# ESPrucherLoraScale7802.net
KiCad netlist of a schematic drawn in EAGLE
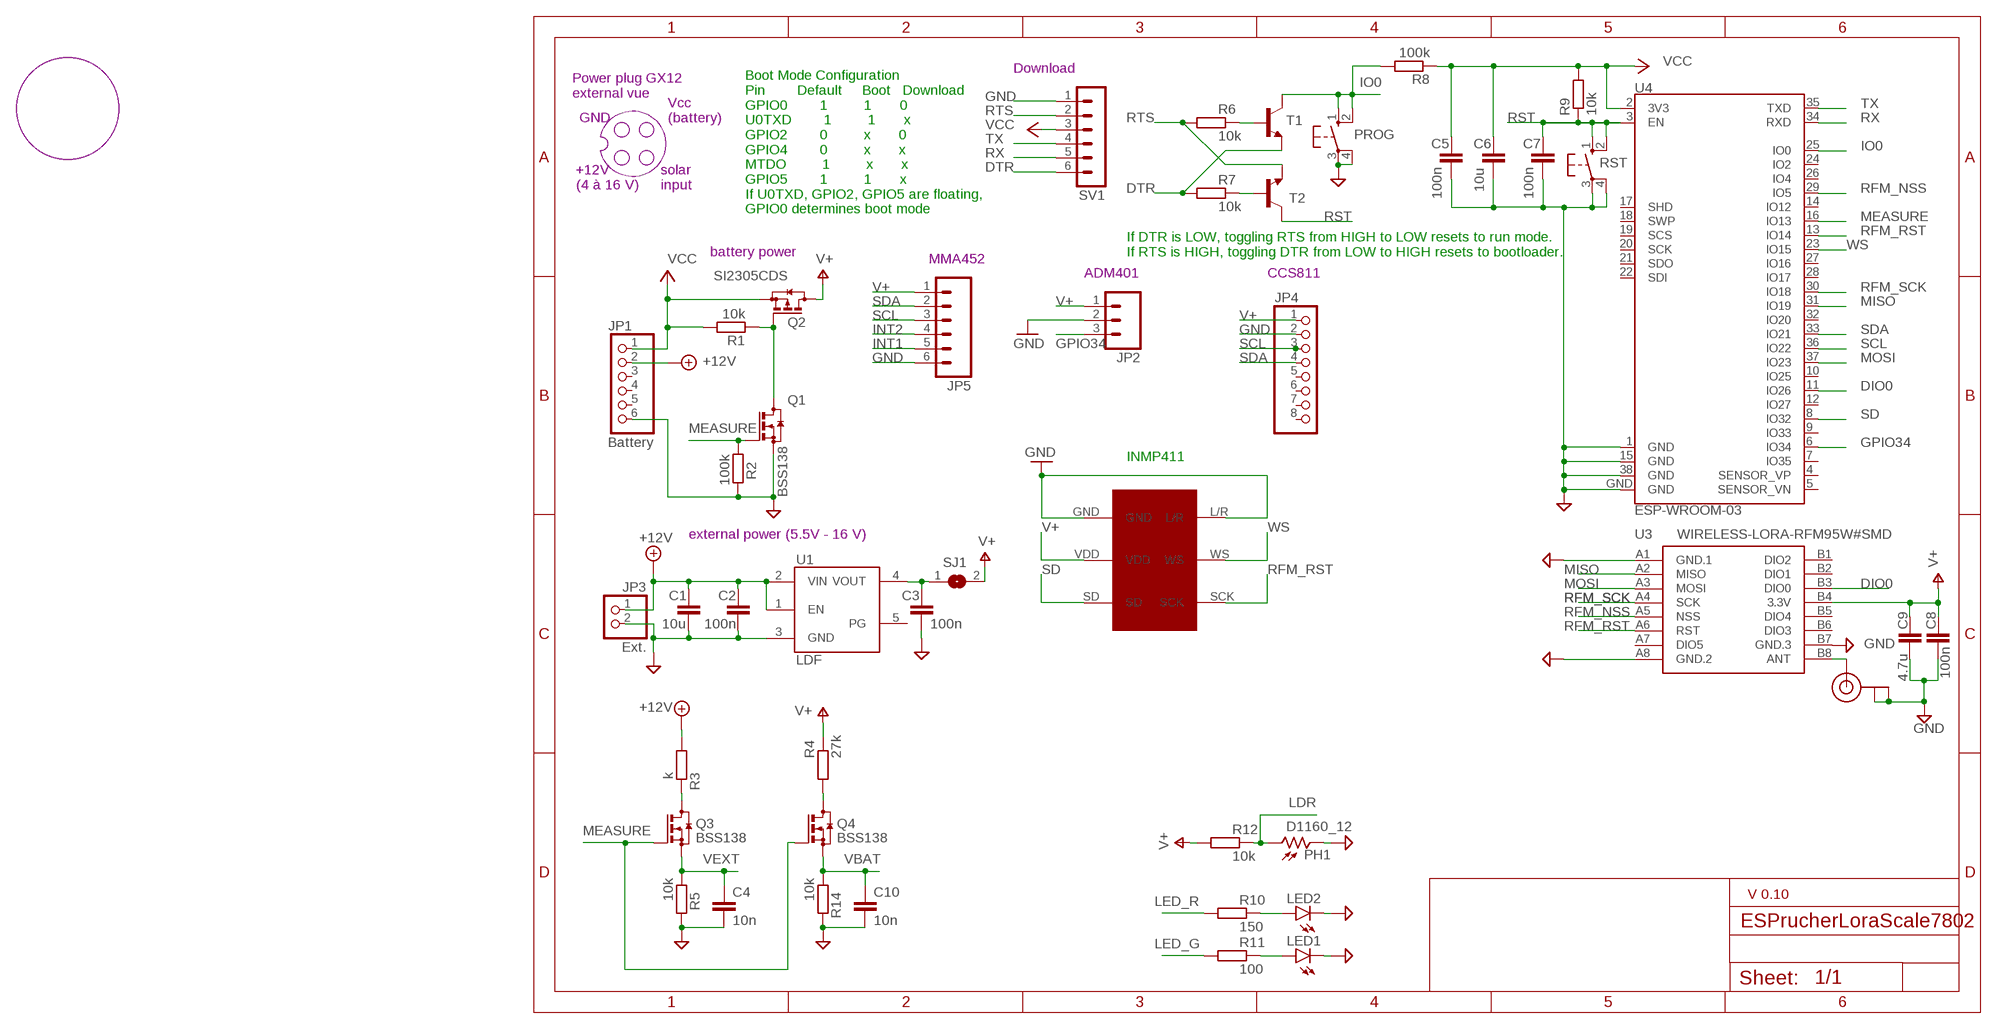
[diagram p0: schematic, sheet 1]

(export (version "E")
  (design (tool "Eeschema 10.0.6"))
  (components
    (comp (ref "C1")
      (value "10u")
      (footprint "eagle-import:C1210")
      (libsource (lib "eagle-import") (part "CC1210"))
    )
    (comp (ref "C2")
      (value "100n")
      (footprint "eagle-import:C1206")
      (libsource (lib "eagle-import") (part "CC1206"))
    )
    (comp (ref "C3")
      (value "100n")
      (footprint "eagle-import:C1206")
      (libsource (lib "eagle-import") (part "CC1206"))
    )
    (comp (ref "C4")
      (value "10n")
      (footprint "eagle-import:C1206")
      (libsource (lib "eagle-import") (part "CC1206"))
    )
    (comp (ref "C5")
      (value "100n")
      (footprint "eagle-import:C1206")
      (libsource (lib "eagle-import") (part "CC1206"))
    )
    (comp (ref "C6")
      (value "10u")
      (footprint "eagle-import:C1210")
      (libsource (lib "eagle-import") (part "CC1210"))
    )
    (comp (ref "C7")
      (value "100n")
      (footprint "eagle-import:C1206")
      (libsource (lib "eagle-import") (part "CC1206"))
    )
    (comp (ref "C8")
      (value "100n")
      (footprint "eagle-import:C1206")
      (libsource (lib "eagle-import") (part "CC1206"))
    )
    (comp (ref "C9")
      (value "4.7u")
      (footprint "eagle-import:C1210")
      (libsource (lib "eagle-import") (part "CC1210"))
    )
    (comp (ref "C10")
      (value "10n")
      (footprint "eagle-import:C1206")
      (libsource (lib "eagle-import") (part "CC1206"))
    )
    (comp (ref "J1")
      (value "U.FL")
      (footprint "eagle-import:U.FL")
      (libsource (lib "eagle-import") (part "U.FL"))
    )
    (comp (ref "JP1")
      (value "Battery")
      (footprint "eagle-import:1X06")
      (libsource (lib "eagle-import") (part "PINHD-1X6"))
    )
    (comp (ref "JP2")
      (value "M03PTH")
      (footprint "eagle-import:1X03")
      (libsource (lib "eagle-import") (part "M03PTH"))
    )
    (comp (ref "JP3")
      (value "Ext.")
      (footprint "eagle-import:1X02")
      (libsource (lib "eagle-import") (part "PINHD-1X2"))
    )
    (comp (ref "JP4")
      (value "HEADER-1X870MIL")
      (footprint "eagle-import:1X08_ROUND_70")
      (libsource (lib "eagle-import") (part "HEADER-1X870MIL"))
    )
    (comp (ref "JP5")
      (value "M06SIP")
      (footprint "eagle-import:1X06")
      (libsource (lib "eagle-import") (part "M06SIP"))
    )
    (comp (ref "LED1")
      (value "LEDCHIPLED_0805")
      (footprint "eagle-import:CHIPLED_0805")
      (libsource (lib "eagle-import") (part "LEDCHIPLED_0805"))
    )
    (comp (ref "LED2")
      (value "LEDCHIPLED_0805")
      (footprint "eagle-import:CHIPLED_0805")
      (libsource (lib "eagle-import") (part "LEDCHIPLED_0805"))
    )
    (comp (ref "PH1")
      (value "D1160_12")
      (footprint "eagle-import:D11XX")
      (libsource (lib "eagle-import") (part "D1160_12"))
    )
    (comp (ref "PROG")
      (value "10-XX")
      (footprint "eagle-import:B3F-10XX")
      (fields (field (name "MPN") "B3F-1000"))
      (libsource (lib "eagle-import") (part "10-XX"))
    )
    (comp (ref "Q1")
      (value "BSS138")
      (footprint "eagle-import:SOT23")
      (libsource (lib "eagle-import") (part "BSS138"))
    )
    (comp (ref "Q2")
      (value "SI2305CDS")
      (footprint "eagle-import:SOT23")
      (libsource (lib "eagle-import") (part "SI2305CDS"))
    )
    (comp (ref "Q3")
      (value "BSS138")
      (footprint "eagle-import:SOT23")
      (libsource (lib "eagle-import") (part "BSS138"))
    )
    (comp (ref "Q4")
      (value "BSS138")
      (footprint "eagle-import:SOT23")
      (libsource (lib "eagle-import") (part "BSS138"))
    )
    (comp (ref "R1")
      (value "10k")
      (footprint "eagle-import:R1206")
      (libsource (lib "eagle-import") (part "RR1206"))
    )
    (comp (ref "R2")
      (value "100k")
      (footprint "eagle-import:R1206")
      (libsource (lib "eagle-import") (part "RR1206"))
    )
    (comp (ref "R3")
      (value "k")
      (footprint "eagle-import:R1206")
      (libsource (lib "eagle-import") (part "RR1206"))
    )
    (comp (ref "R4")
      (value "27k")
      (footprint "eagle-import:R1206")
      (libsource (lib "eagle-import") (part "RR1206"))
    )
    (comp (ref "R5")
      (value "10k")
      (footprint "eagle-import:R1206")
      (libsource (lib "eagle-import") (part "RR1206"))
    )
    (comp (ref "R6")
      (value "10k")
      (footprint "eagle-import:R1206")
      (libsource (lib "eagle-import") (part "RR1206"))
    )
    (comp (ref "R7")
      (value "10k")
      (footprint "eagle-import:R1206")
      (libsource (lib "eagle-import") (part "RR1206"))
    )
    (comp (ref "R8")
      (value "100k")
      (footprint "eagle-import:R1206")
      (libsource (lib "eagle-import") (part "RR1206"))
    )
    (comp (ref "R9")
      (value "10k")
      (footprint "eagle-import:R1206")
      (libsource (lib "eagle-import") (part "RR1206"))
    )
    (comp (ref "R10")
      (value "150")
      (footprint "eagle-import:R1206")
      (libsource (lib "eagle-import") (part "RR1206"))
    )
    (comp (ref "R11")
      (value "100")
      (footprint "eagle-import:R1206")
      (libsource (lib "eagle-import") (part "RR1206"))
    )
    (comp (ref "R12")
      (value "10k")
      (footprint "eagle-import:R1206")
      (libsource (lib "eagle-import") (part "RR1206"))
    )
    (comp (ref "R14")
      (value "10k")
      (footprint "eagle-import:R1206")
      (libsource (lib "eagle-import") (part "RR1206"))
    )
    (comp (ref "RST")
      (value "10-XX")
      (footprint "eagle-import:B3F-10XX")
      (fields (field (name "MPN") "B3F-1000"))
      (libsource (lib "eagle-import") (part "10-XX"))
    )
    (comp (ref "SJ1")
      (value "SJW")
      (footprint "eagle-import:SJW")
      (libsource (lib "eagle-import") (part "SJW"))
    )
    (comp (ref "SV1")
      (value "MA06-1")
      (footprint "eagle-import:MA06-1")
      (libsource (lib "eagle-import") (part "MA06-1"))
    )
    (comp (ref "T1")
      (value "MMBT2222ALT1-NPN-SOT23-BEC")
      (footprint "eagle-import:SOT23-BEC")
      (libsource (lib "eagle-import") (part "-NPN-SOT23-BECMMBT2222ALT1"))
    )
    (comp (ref "T2")
      (value "MMBT2222ALT1-NPN-SOT23-BEC")
      (footprint "eagle-import:SOT23-BEC")
      (libsource (lib "eagle-import") (part "-NPN-SOT23-BECMMBT2222ALT1"))
    )
    (comp (ref "U$1")
      (value "INMP411")
      (footprint "eagle-import:INMP411FOOTPRINT")
      (libsource (lib "eagle-import") (part "INMP411"))
    )
    (comp (ref "U1")
      (value "LDF3.3")
      (footprint "eagle-import:PPAK")
      (libsource (lib "eagle-import") (part "LDF3.3"))
    )
    (comp (ref "U3")
      (value "WIRELESS-LORA-RFM95W#SMD")
      (footprint "eagle-import:WIRELESS-LORA-RFM95W#SMD")
      (libsource (lib "eagle-import") (part "WIRELESS-LORA-RFM95W#SMD"))
    )
    (comp (ref "U4")
      (value "ESP-WROOM-03")
      (footprint "eagle-import:ESP-WROOM-03")
      (libsource (lib "eagle-import") (part "ESP-WROOM-03"))
    )
  )
  (nets
    (net (code "1") (name "+12V") (class "Default")
      (node (ref "C1") (pin "1") (pinfunction "1_1") (pintype "passive"))
      (node (ref "C2") (pin "1") (pinfunction "1_1") (pintype "passive"))
      (node (ref "JP1") (pin "2") (pinfunction "2_2") (pintype "passive"))
      (node (ref "JP3") (pin "1") (pinfunction "1_1") (pintype "passive"))
      (node (ref "R3") (pin "1") (pinfunction "1_1") (pintype "passive"))
      (node (ref "U1") (pin "1") (pinfunction "EN_1") (pintype "input"))
      (node (ref "U1") (pin "2") (pinfunction "VIN_2") (pintype "power_in"))
    )
    (net (code "2") (name "/DIO0") (class "Default")
      (node (ref "U3") (pin "B3") (pinfunction "DIO0_B3") (pintype "bidirectional"))
      (node (ref "U4") (pin "11") (pinfunction "IO26_11") (pintype "bidirectional"))
    )
    (net (code "3") (name "/DTR") (class "Default")
      (node (ref "R7") (pin "1") (pinfunction "1_1") (pintype "passive"))
      (node (ref "SV1") (pin "6") (pinfunction "6_6") (pintype "passive"))
      (node (ref "T1") (pin "E") (pinfunction "E_E") (pintype "passive"))
    )
    (net (code "4") (name "/GPIO34") (class "Default")
      (node (ref "JP2") (pin "3") (pinfunction "3_3") (pintype "passive"))
      (node (ref "U4") (pin "6") (pinfunction "IO34_6") (pintype "bidirectional"))
    )
    (net (code "5") (name "/INT1") (class "Default")
      (node (ref "JP5") (pin "5") (pinfunction "5_5") (pintype "passive"))
    )
    (net (code "6") (name "/INT2") (class "Default")
      (node (ref "JP5") (pin "4") (pinfunction "4_4") (pintype "passive"))
    )
    (net (code "7") (name "/IO0") (class "Default")
      (node (ref "PROG") (pin "1") (pinfunction "S_1") (pintype "passive"))
      (node (ref "PROG") (pin "2") (pinfunction "S1_2") (pintype "passive"))
      (node (ref "R8") (pin "2") (pinfunction "2_2") (pintype "passive"))
      (node (ref "T1") (pin "C") (pinfunction "C_C") (pintype "passive"))
      (node (ref "U4") (pin "25") (pinfunction "IO0_25") (pintype "bidirectional"))
    )
    (net (code "8") (name "/LDR") (class "Default")
      (node (ref "PH1") (pin "1") (pinfunction "1_1") (pintype "passive"))
      (node (ref "R12") (pin "2") (pinfunction "2_2") (pintype "passive"))
    )
    (net (code "9") (name "/LED_G") (class "Default")
      (node (ref "R11") (pin "1") (pinfunction "1_1") (pintype "passive"))
    )
    (net (code "10") (name "/LED_R") (class "Default")
      (node (ref "R10") (pin "1") (pinfunction "1_1") (pintype "passive"))
    )
    (net (code "11") (name "/MEASURE") (class "Default")
      (node (ref "Q1") (pin "1") (pinfunction "G_1") (pintype "passive"))
      (node (ref "Q3") (pin "1") (pinfunction "G_1") (pintype "passive"))
      (node (ref "Q4") (pin "1") (pinfunction "G_1") (pintype "passive"))
      (node (ref "R2") (pin "1") (pinfunction "1_1") (pintype "passive"))
      (node (ref "U4") (pin "16") (pinfunction "IO13_16") (pintype "bidirectional"))
    )
    (net (code "12") (name "/MISO") (class "Default")
      (node (ref "U3") (pin "A2") (pinfunction "MISO_A2") (pintype "bidirectional"))
      (node (ref "U4") (pin "31") (pinfunction "IO19_31") (pintype "bidirectional"))
    )
    (net (code "13") (name "/MOSI") (class "Default")
      (node (ref "U3") (pin "A3") (pinfunction "MOSI_A3") (pintype "bidirectional"))
      (node (ref "U4") (pin "37") (pinfunction "IO23_37") (pintype "bidirectional"))
    )
    (net (code "14") (name "/PG") (class "Default")
      (node (ref "U1") (pin "5") (pinfunction "PG_5") (pintype "power_in"))
    )
    (net (code "15") (name "/RFM_NSS") (class "Default")
      (node (ref "U3") (pin "A5") (pinfunction "NSS_A5") (pintype "bidirectional"))
      (node (ref "U4") (pin "29") (pinfunction "IO5_29") (pintype "bidirectional"))
    )
    (net (code "16") (name "/RFM_RST") (class "Default")
      (node (ref "U$1") (pin "SCK") (pinfunction "SCK_SCK") (pintype "bidirectional"))
      (node (ref "U3") (pin "A6") (pinfunction "RST_A6") (pintype "bidirectional"))
      (node (ref "U4") (pin "13") (pinfunction "IO14_13") (pintype "bidirectional"))
    )
    (net (code "17") (name "/RFM_SCK") (class "Default")
      (node (ref "U3") (pin "A4") (pinfunction "SCK_A4") (pintype "bidirectional"))
      (node (ref "U4") (pin "30") (pinfunction "IO18_30") (pintype "bidirectional"))
    )
    (net (code "18") (name "/RST") (class "Default")
      (node (ref "C7") (pin "1") (pinfunction "1_1") (pintype "passive"))
      (node (ref "R9") (pin "1") (pinfunction "1_1") (pintype "passive"))
      (node (ref "RST") (pin "1") (pinfunction "S_1") (pintype "passive"))
      (node (ref "RST") (pin "2") (pinfunction "S1_2") (pintype "passive"))
      (node (ref "T2") (pin "C") (pinfunction "C_C") (pintype "passive"))
      (node (ref "U4") (pin "3") (pinfunction "EN_3") (pintype "bidirectional"))
    )
    (net (code "19") (name "/RTS") (class "Default")
      (node (ref "R6") (pin "1") (pinfunction "1_1") (pintype "passive"))
      (node (ref "SV1") (pin "2") (pinfunction "2_2") (pintype "passive"))
      (node (ref "T2") (pin "E") (pinfunction "E_E") (pintype "passive"))
    )
    (net (code "20") (name "/RX") (class "Default")
      (node (ref "SV1") (pin "5") (pinfunction "5_5") (pintype "passive"))
      (node (ref "U4") (pin "34") (pinfunction "RXD_34") (pintype "bidirectional"))
    )
    (net (code "21") (name "/SCL") (class "Default")
      (node (ref "JP4") (pin "3") (pinfunction "3_3") (pintype "passive"))
      (node (ref "JP5") (pin "3") (pinfunction "3_3") (pintype "passive"))
      (node (ref "U4") (pin "36") (pinfunction "IO22_36") (pintype "bidirectional"))
    )
    (net (code "22") (name "/SD") (class "Default")
      (node (ref "U$1") (pin "SD") (pinfunction "SD_SD") (pintype "bidirectional"))
      (node (ref "U4") (pin "8") (pinfunction "IO32_8") (pintype "bidirectional"))
    )
    (net (code "23") (name "/SDA") (class "Default")
      (node (ref "JP4") (pin "4") (pinfunction "4_4") (pintype "passive"))
      (node (ref "JP5") (pin "2") (pinfunction "2_2") (pintype "passive"))
      (node (ref "U4") (pin "33") (pinfunction "IO21_33") (pintype "bidirectional"))
    )
    (net (code "24") (name "/TX") (class "Default")
      (node (ref "SV1") (pin "4") (pinfunction "4_4") (pintype "passive"))
      (node (ref "U4") (pin "35") (pinfunction "TXD_35") (pintype "bidirectional"))
    )
    (net (code "25") (name "/VBAT") (class "Default")
      (node (ref "C10") (pin "1") (pinfunction "1_1") (pintype "passive"))
      (node (ref "Q4") (pin "2") (pinfunction "S_2") (pintype "passive"))
      (node (ref "R14") (pin "1") (pinfunction "1_1") (pintype "passive"))
    )
    (net (code "26") (name "/VEXT") (class "Default")
      (node (ref "C4") (pin "1") (pinfunction "1_1") (pintype "passive"))
      (node (ref "Q3") (pin "2") (pinfunction "S_2") (pintype "passive"))
      (node (ref "R5") (pin "1") (pinfunction "1_1") (pintype "passive"))
    )
    (net (code "27") (name "/WS") (class "Default")
      (node (ref "U$1") (pin "WS") (pinfunction "WS_WS") (pintype "bidirectional"))
      (node (ref "U4") (pin "23") (pinfunction "IO15_23") (pintype "bidirectional"))
    )
    (net (code "28") (name "GND") (class "Default")
      (node (ref "C1") (pin "2") (pinfunction "2_2") (pintype "passive"))
      (node (ref "C10") (pin "2") (pinfunction "2_2") (pintype "passive"))
      (node (ref "C2") (pin "2") (pinfunction "2_2") (pintype "passive"))
      (node (ref "C3") (pin "2") (pinfunction "2_2") (pintype "passive"))
      (node (ref "C4") (pin "2") (pinfunction "2_2") (pintype "passive"))
      (node (ref "C5") (pin "2") (pinfunction "2_2") (pintype "passive"))
      (node (ref "C6") (pin "2") (pinfunction "2_2") (pintype "passive"))
      (node (ref "C7") (pin "2") (pinfunction "2_2") (pintype "passive"))
      (node (ref "C8") (pin "2") (pinfunction "2_2") (pintype "passive"))
      (node (ref "C9") (pin "2") (pinfunction "2_2") (pintype "passive"))
      (node (ref "J1") (pin "1") (pinfunction "GND_1") (pintype "passive"))
      (node (ref "J1") (pin "2") (pinfunction "GND_2") (pintype "passive"))
      (node (ref "JP1") (pin "6") (pinfunction "6_6") (pintype "passive"))
      (node (ref "JP2") (pin "2") (pinfunction "2_2") (pintype "passive"))
      (node (ref "JP3") (pin "2") (pinfunction "2_2") (pintype "passive"))
      (node (ref "JP4") (pin "2") (pinfunction "2_2") (pintype "passive"))
      (node (ref "JP5") (pin "6") (pinfunction "6_6") (pintype "passive"))
      (node (ref "LED1") (pin "C") (pinfunction "C_C") (pintype "passive"))
      (node (ref "LED2") (pin "C") (pinfunction "C_C") (pintype "passive"))
      (node (ref "PH1") (pin "2") (pinfunction "2_2") (pintype "passive"))
      (node (ref "PROG") (pin "3") (pinfunction "P_3") (pintype "passive"))
      (node (ref "PROG") (pin "4") (pinfunction "P1_4") (pintype "passive"))
      (node (ref "Q1") (pin "2") (pinfunction "S_2") (pintype "passive"))
      (node (ref "R14") (pin "2") (pinfunction "2_2") (pintype "passive"))
      (node (ref "R2") (pin "2") (pinfunction "2_2") (pintype "passive"))
      (node (ref "R5") (pin "2") (pinfunction "2_2") (pintype "passive"))
      (node (ref "RST") (pin "3") (pinfunction "P_3") (pintype "passive"))
      (node (ref "RST") (pin "4") (pinfunction "P1_4") (pintype "passive"))
      (node (ref "SV1") (pin "1") (pinfunction "1_1") (pintype "passive"))
      (node (ref "U$1") (pin "GND") (pinfunction "GND_GND") (pintype "bidirectional"))
      (node (ref "U$1") (pin "L/R") (pinfunction "L/R_L/R") (pintype "bidirectional"))
      (node (ref "U1") (pin "3") (pinfunction "GND_3") (pintype "power_in"))
      (node (ref "U3") (pin "A1") (pinfunction "GND.1_A1") (pintype "power_in"))
      (node (ref "U3") (pin "A8") (pinfunction "GND.2_A8") (pintype "power_in"))
      (node (ref "U3") (pin "B7") (pinfunction "GND.3_B7") (pintype "power_in"))
      (node (ref "U4") (pin "1") (pinfunction "GND_1") (pintype "bidirectional"))
      (node (ref "U4") (pin "15") (pinfunction "GND_15") (pintype "bidirectional"))
      (node (ref "U4") (pin "38") (pinfunction "GND_38") (pintype "bidirectional"))
      (node (ref "U4") (pin "GND") (pinfunction "GND_GND") (pintype "bidirectional"))
    )
    (net (code "29") (name "Net-(J1-SIGNAL)") (class "Default")
      (node (ref "J1") (pin "3") (pinfunction "SIGNAL_3") (pintype "passive"))
      (node (ref "U3") (pin "B8") (pinfunction "ANT_B8") (pintype "passive"))
    )
    (net (code "30") (name "Net-(LED1-PadA)") (class "Default")
      (node (ref "LED1") (pin "A") (pinfunction "A_A") (pintype "passive"))
      (node (ref "R11") (pin "2") (pinfunction "2_2") (pintype "passive"))
    )
    (net (code "31") (name "Net-(LED2-PadA)") (class "Default")
      (node (ref "LED2") (pin "A") (pinfunction "A_A") (pintype "passive"))
      (node (ref "R10") (pin "2") (pinfunction "2_2") (pintype "passive"))
    )
    (net (code "32") (name "Net-(Q1-D)") (class "Default")
      (node (ref "Q1") (pin "3") (pinfunction "D_3") (pintype "passive"))
      (node (ref "Q2") (pin "1") (pinfunction "G_1") (pintype "passive"))
      (node (ref "R1") (pin "1") (pinfunction "1_1") (pintype "passive"))
    )
    (net (code "33") (name "Net-(Q3-D)") (class "Default")
      (node (ref "Q3") (pin "3") (pinfunction "D_3") (pintype "passive"))
      (node (ref "R3") (pin "2") (pinfunction "2_2") (pintype "passive"))
    )
    (net (code "34") (name "Net-(Q4-D)") (class "Default")
      (node (ref "Q4") (pin "3") (pinfunction "D_3") (pintype "passive"))
      (node (ref "R4") (pin "1") (pinfunction "1_1") (pintype "passive"))
    )
    (net (code "35") (name "Net-(R6-Pad2)") (class "Default")
      (node (ref "R6") (pin "2") (pinfunction "2_2") (pintype "passive"))
      (node (ref "T1") (pin "B") (pinfunction "B_B") (pintype "passive"))
    )
    (net (code "36") (name "Net-(R7-Pad2)") (class "Default")
      (node (ref "R7") (pin "2") (pinfunction "2_2") (pintype "passive"))
      (node (ref "T2") (pin "B") (pinfunction "B_B") (pintype "passive"))
    )
    (net (code "37") (name "Net-(U1-VOUT)") (class "Default")
      (node (ref "C3") (pin "1") (pinfunction "1_1") (pintype "passive"))
      (node (ref "SJ1") (pin "1") (pinfunction "1_1") (pintype "passive"))
      (node (ref "U1") (pin "4") (pinfunction "VOUT_4") (pintype "power_in"))
    )
    (net (code "38") (name "V+") (class "Default")
      (node (ref "C8") (pin "1") (pinfunction "1_1") (pintype "passive"))
      (node (ref "C9") (pin "1") (pinfunction "1_1") (pintype "passive"))
      (node (ref "JP2") (pin "1") (pinfunction "1_1") (pintype "passive"))
      (node (ref "JP4") (pin "1") (pinfunction "1_1") (pintype "passive"))
      (node (ref "JP5") (pin "1") (pinfunction "1_1") (pintype "passive"))
      (node (ref "Q2") (pin "3") (pinfunction "D_3") (pintype "passive"))
      (node (ref "R12") (pin "1") (pinfunction "1_1") (pintype "passive"))
      (node (ref "R4") (pin "2") (pinfunction "2_2") (pintype "passive"))
      (node (ref "SJ1") (pin "2") (pinfunction "2_2") (pintype "passive"))
      (node (ref "U$1") (pin "VDD") (pinfunction "VDD_VDD") (pintype "bidirectional"))
      (node (ref "U3") (pin "B4") (pinfunction "3.3V_B4") (pintype "power_in"))
    )
    (net (code "39") (name "VCC") (class "Default")
      (node (ref "C5") (pin "1") (pinfunction "1_1") (pintype "passive"))
      (node (ref "C6") (pin "1") (pinfunction "1_1") (pintype "passive"))
      (node (ref "JP1") (pin "1") (pinfunction "1_1") (pintype "passive"))
      (node (ref "Q2") (pin "2") (pinfunction "S_2") (pintype "passive"))
      (node (ref "R1") (pin "2") (pinfunction "2_2") (pintype "passive"))
      (node (ref "R8") (pin "1") (pinfunction "1_1") (pintype "passive"))
      (node (ref "R9") (pin "2") (pinfunction "2_2") (pintype "passive"))
      (node (ref "SV1") (pin "3") (pinfunction "3_3") (pintype "passive"))
      (node (ref "U4") (pin "2") (pinfunction "3V3_2") (pintype "bidirectional"))
    )
    (net (code "40") (name "unconnected-(JP1-Pad3)") (class "Default")
      (node (ref "JP1") (pin "3") (pinfunction "3_3") (pintype "passive"))
    )
    (net (code "41") (name "unconnected-(JP1-Pad4)") (class "Default")
      (node (ref "JP1") (pin "4") (pinfunction "4_4") (pintype "passive"))
    )
    (net (code "42") (name "unconnected-(JP1-Pad5)") (class "Default")
      (node (ref "JP1") (pin "5") (pinfunction "5_5") (pintype "passive"))
    )
    (net (code "43") (name "unconnected-(JP4-Pad5)") (class "Default")
      (node (ref "JP4") (pin "5") (pinfunction "5_5") (pintype "passive"))
    )
    (net (code "44") (name "unconnected-(JP4-Pad6)") (class "Default")
      (node (ref "JP4") (pin "6") (pinfunction "6_6") (pintype "passive"))
    )
    (net (code "45") (name "unconnected-(JP4-Pad7)") (class "Default")
      (node (ref "JP4") (pin "7") (pinfunction "7_7") (pintype "passive"))
    )
    (net (code "46") (name "unconnected-(JP4-Pad8)") (class "Default")
      (node (ref "JP4") (pin "8") (pinfunction "8_8") (pintype "passive"))
    )
    (net (code "47") (name "unconnected-(U3-DIO1-PadB2)") (class "Default")
      (node (ref "U3") (pin "B2") (pinfunction "DIO1_B2") (pintype "bidirectional"))
    )
    (net (code "48") (name "unconnected-(U3-DIO2-PadB1)") (class "Default")
      (node (ref "U3") (pin "B1") (pinfunction "DIO2_B1") (pintype "bidirectional"))
    )
    (net (code "49") (name "unconnected-(U3-DIO3-PadB6)") (class "Default")
      (node (ref "U3") (pin "B6") (pinfunction "DIO3_B6") (pintype "bidirectional"))
    )
    (net (code "50") (name "unconnected-(U3-DIO4-PadB5)") (class "Default")
      (node (ref "U3") (pin "B5") (pinfunction "DIO4_B5") (pintype "bidirectional"))
    )
    (net (code "51") (name "unconnected-(U3-DIO5-PadA7)") (class "Default")
      (node (ref "U3") (pin "A7") (pinfunction "DIO5_A7") (pintype "bidirectional"))
    )
    (net (code "52") (name "unconnected-(U4-IO2-Pad24)") (class "Default")
      (node (ref "U4") (pin "24") (pinfunction "IO2_24") (pintype "bidirectional"))
    )
    (net (code "53") (name "unconnected-(U4-IO4-Pad26)") (class "Default")
      (node (ref "U4") (pin "26") (pinfunction "IO4_26") (pintype "bidirectional"))
    )
    (net (code "54") (name "unconnected-(U4-IO12-Pad14)") (class "Default")
      (node (ref "U4") (pin "14") (pinfunction "IO12_14") (pintype "bidirectional"))
    )
    (net (code "55") (name "unconnected-(U4-IO16-Pad27)") (class "Default")
      (node (ref "U4") (pin "27") (pinfunction "IO16_27") (pintype "bidirectional"))
    )
    (net (code "56") (name "unconnected-(U4-IO17-Pad28)") (class "Default")
      (node (ref "U4") (pin "28") (pinfunction "IO17_28") (pintype "bidirectional"))
    )
    (net (code "57") (name "unconnected-(U4-IO20-Pad32)") (class "Default")
      (node (ref "U4") (pin "32") (pinfunction "IO20_32") (pintype "bidirectional"))
    )
    (net (code "58") (name "unconnected-(U4-IO25-Pad10)") (class "Default")
      (node (ref "U4") (pin "10") (pinfunction "IO25_10") (pintype "bidirectional"))
    )
    (net (code "59") (name "unconnected-(U4-IO27-Pad12)") (class "Default")
      (node (ref "U4") (pin "12") (pinfunction "IO27_12") (pintype "bidirectional"))
    )
    (net (code "60") (name "unconnected-(U4-IO33-Pad9)") (class "Default")
      (node (ref "U4") (pin "9") (pinfunction "IO33_9") (pintype "bidirectional"))
    )
    (net (code "61") (name "unconnected-(U4-IO35-Pad7)") (class "Default")
      (node (ref "U4") (pin "7") (pinfunction "IO35_7") (pintype "bidirectional"))
    )
    (net (code "62") (name "unconnected-(U4-SCK-Pad20)") (class "Default")
      (node (ref "U4") (pin "20") (pinfunction "SCK_20") (pintype "bidirectional"))
    )
    (net (code "63") (name "unconnected-(U4-SCS-Pad19)") (class "Default")
      (node (ref "U4") (pin "19") (pinfunction "SCS_19") (pintype "bidirectional"))
    )
    (net (code "64") (name "unconnected-(U4-SDI-Pad22)") (class "Default")
      (node (ref "U4") (pin "22") (pinfunction "SDI_22") (pintype "bidirectional"))
    )
    (net (code "65") (name "unconnected-(U4-SDO-Pad21)") (class "Default")
      (node (ref "U4") (pin "21") (pinfunction "SDO_21") (pintype "bidirectional"))
    )
    (net (code "66") (name "unconnected-(U4-SENSOR_VN-Pad5)") (class "Default")
      (node (ref "U4") (pin "5") (pinfunction "SENSOR_VN_5") (pintype "bidirectional"))
    )
    (net (code "67") (name "unconnected-(U4-SENSOR_VP-Pad4)") (class "Default")
      (node (ref "U4") (pin "4") (pinfunction "SENSOR_VP_4") (pintype "bidirectional"))
    )
    (net (code "68") (name "unconnected-(U4-SHD-Pad17)") (class "Default")
      (node (ref "U4") (pin "17") (pinfunction "SHD_17") (pintype "bidirectional"))
    )
    (net (code "69") (name "unconnected-(U4-SWP-Pad18)") (class "Default")
      (node (ref "U4") (pin "18") (pinfunction "SWP_18") (pintype "bidirectional"))
    )
  )
)
